# SlotCarChannel.net
KiCad netlist of a schematic drawn in Altium Designer
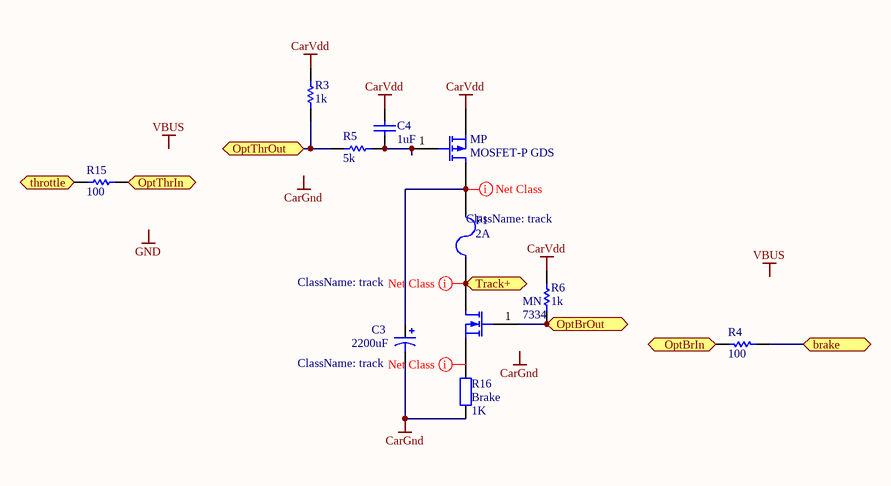
[diagram p0: SlotCarChannel.SchDoc]

(export (version "E")
  (design (tool "Eeschema 10.0.6"))
  (components
    (comp (ref "C3")
      (value "2200uF")
      (footprint "CAPPR5-12.5x35")
      (description "Polarized Capacitor (Radial)")
      (fields (field (name "PUBLISHER") "Altium Limited"))
      (libsource (lib "Miscellaneous Devices") (part "Cap Pol1"))
    )
    (comp (ref "C4")
      (value "1uF")
      (footprint "CC1608-0603")
      (description "Capacitor (Semiconductor SIM Model)")
      (fields (field (name "PUBLISHER") "Altium Limited"))
      (libsource (lib "Miscellaneous Devices") (part "Cap Semi"))
    )
    (comp (ref "F1")
      (value "2A")
      (footprint "2920Littelfuse")
      (description "Fuse")
      (fields (field (name "PUBLISHER") "Altium Limited"))
      (libsource (lib "Miscellaneous Devices") (part "Fuse 2"))
    )
    (comp (ref "MN")
      (value "7334")
      (footprint "TO220_HEATSINK")
      (description "N-Channel MOSFET")
      (fields (field (name "PUBLISHER") "Altium Limited"))
      (libsource (lib "SlotCarController") (part "MOSFET-N-GDS"))
    )
    (comp (ref "MP")
      (value "MOSFET-P GDS")
      (footprint "tilepcb:TO220_HEATSINK")
      (description "P-Channel MOSFET")
      (fields (field (name "PUBLISHER") "Altium Limited"))
      (libsource (lib "SlotCarController") (part "MOSFET-P-GDS"))
    )
    (comp (ref "R3")
      (value "1k")
      (footprint "CR1608-0603")
      (description "Semiconductor Resistor")
      (fields (field (name "PUBLISHER") "Altium Limited"))
      (libsource (lib "Miscellaneous Devices") (part "Res Semi"))
    )
    (comp (ref "R4")
      (value "100")
      (footprint "CR1608-0603")
      (description "Semiconductor Resistor")
      (fields (field (name "PUBLISHER") "Altium Limited"))
      (libsource (lib "Miscellaneous Devices") (part "Res Semi"))
    )
    (comp (ref "R5")
      (value "5k")
      (footprint "CR1608-0603")
      (description "Semiconductor Resistor")
      (fields (field (name "PUBLISHER") "Altium Limited"))
      (libsource (lib "Miscellaneous Devices") (part "Res Semi"))
    )
    (comp (ref "R6")
      (value "1k")
      (footprint "CR1608-0603")
      (description "Semiconductor Resistor")
      (fields (field (name "PUBLISHER") "Altium Limited"))
      (libsource (lib "Miscellaneous Devices") (part "Res Semi"))
    )
    (comp (ref "R15")
      (value "100")
      (footprint "CR1608-0603")
      (description "Semiconductor Resistor")
      (fields (field (name "PUBLISHER") "Altium Limited"))
      (libsource (lib "Miscellaneous Devices") (part "Res Semi"))
    )
    (comp (ref "R16")
      (value "Brake")
      (footprint "Axial 0.4")
      (description "Resistor")
      (fields (field (name "ALTIUM_VALUE") "1K") (field (name "PUBLISHER") "Altium Limited"))
      (libsource (lib "Miscellaneous Devices") (part "Res2"))
    )
  )
  (nets
    (net (code "1") (name "/OptBrIn") (class "Default")
      (node (ref "R4") (pin "2") (pinfunction "2_2") (pintype "passive"))
    )
    (net (code "2") (name "/OptBrOut") (class "Default")
      (node (ref "MN") (pin "1") (pinfunction "G_1") (pintype "passive"))
      (node (ref "R6") (pin "2") (pinfunction "2_2") (pintype "passive"))
    )
    (net (code "3") (name "/OptThrIn") (class "Default")
      (node (ref "R15") (pin "2") (pinfunction "2_2") (pintype "passive"))
    )
    (net (code "4") (name "/OptThrOut") (class "Default")
      (node (ref "R3") (pin "2") (pinfunction "2_2") (pintype "passive"))
      (node (ref "R5") (pin "2") (pinfunction "2_2") (pintype "passive"))
    )
    (net (code "5") (name "/Track+") (class "Default")
      (node (ref "F1") (pin "1") (pinfunction "1_1") (pintype "passive"))
      (node (ref "MN") (pin "2") (pinfunction "D_2") (pintype "passive"))
    )
    (net (code "6") (name "/brake") (class "Default")
      (node (ref "R4") (pin "1") (pinfunction "1_1") (pintype "passive"))
    )
    (net (code "7") (name "/throttle") (class "Default")
      (node (ref "R15") (pin "1") (pinfunction "1_1") (pintype "passive"))
    )
    (net (code "8") (name "CarGnd") (class "Default")
      (node (ref "C3") (pin "2") (pinfunction "2_2") (pintype "passive"))
      (node (ref "R16") (pin "1") (pinfunction "1_1") (pintype "passive"))
    )
    (net (code "9") (name "CarVdd") (class "Default")
      (node (ref "C4") (pin "2") (pinfunction "2_2") (pintype "passive"))
      (node (ref "MP") (pin "3") (pinfunction "S_3") (pintype "passive"))
      (node (ref "R3") (pin "1") (pinfunction "1_1") (pintype "passive"))
      (node (ref "R6") (pin "1") (pinfunction "1_1") (pintype "passive"))
    )
    (net (code "11") (name "Net-(MN-S)") (class "Default")
      (node (ref "MN") (pin "3") (pinfunction "S_3") (pintype "passive"))
      (node (ref "R16") (pin "2") (pinfunction "2_2") (pintype "passive"))
    )
    (net (code "12") (name "Net-(MP-D)") (class "Default")
      (node (ref "C3") (pin "1") (pinfunction "1_1") (pintype "passive"))
      (node (ref "F1") (pin "2") (pinfunction "2_2") (pintype "passive"))
      (node (ref "MP") (pin "2") (pinfunction "D_2") (pintype "passive"))
    )
    (net (code "13") (name "Net-(MP-G)") (class "Default")
      (node (ref "C4") (pin "1") (pinfunction "1_1") (pintype "passive"))
      (node (ref "MP") (pin "1") (pinfunction "G_1") (pintype "passive"))
      (node (ref "R5") (pin "1") (pinfunction "1_1") (pintype "passive"))
    )
  )
)
